# hv_psu_v100_MCU.net
KiCad netlist of a schematic drawn in Altium Designer
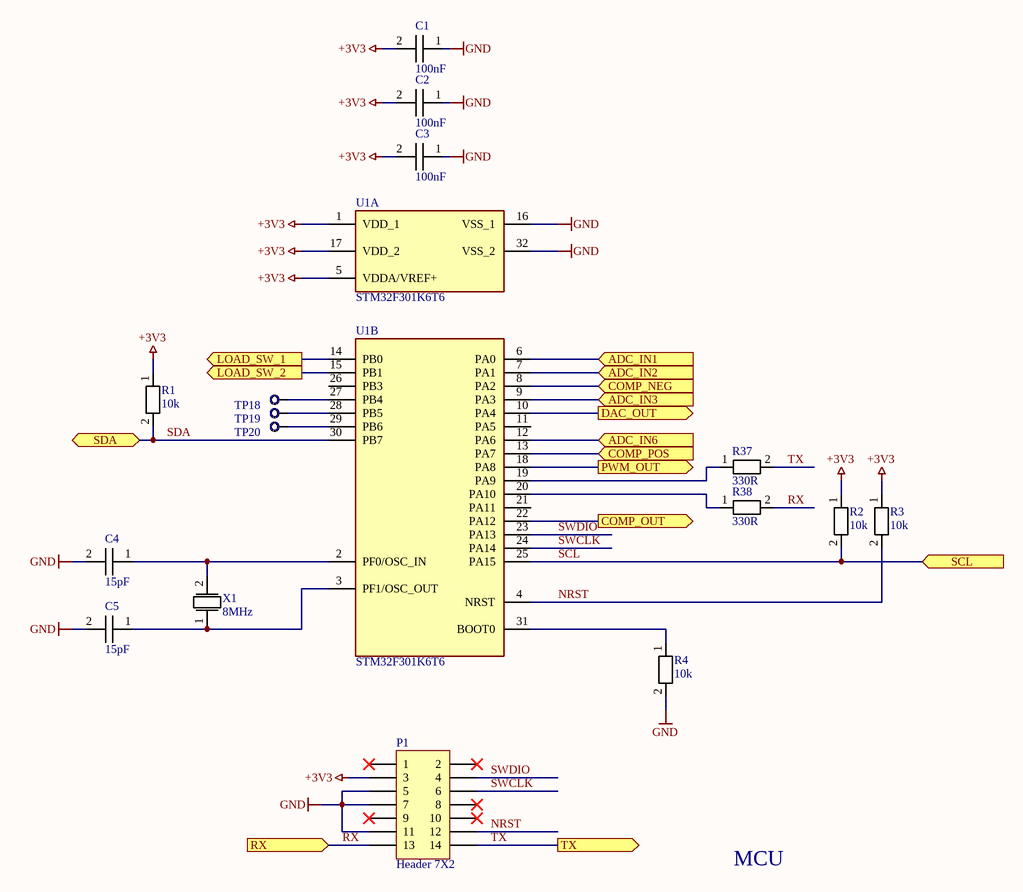
[diagram p0: hv_psu_v100_MCU.SchDoc]

(export (version "E")
  (design (tool "Eeschema 10.0.6"))
  (components
    (comp (ref "C1") (value "100nF") (footprint "1206_C") (libsource (lib "Schlib1") (part "CAPACITOR")))
    (comp (ref "C2") (value "100nF") (footprint "1206_C") (libsource (lib "Schlib1") (part "CAPACITOR")))
    (comp (ref "C3") (value "100nF") (footprint "1206_C") (libsource (lib "Schlib1") (part "CAPACITOR")))
    (comp (ref "C4") (value "15pF") (footprint "1206_C") (libsource (lib "Schlib1") (part "CAPACITOR")))
    (comp (ref "C5") (value "15pF") (footprint "1206_C") (libsource (lib "Schlib1") (part "CAPACITOR")))
    (comp (ref "P1")
      (value "Header 7X2")
      (footprint "HDR2X7")
      (description "Header, 7-Pin, Dual row")
      (fields (field (name "PUBLISHER") "Altium Limited"))
      (libsource (lib "Miscellaneous Connectors") (part "Header 7X2"))
    )
    (comp (ref "R1") (value "10k") (footprint "1206") (libsource (lib "Schlib1") (part "RESISTOR")))
    (comp (ref "R2") (value "10k") (footprint "1206") (libsource (lib "Schlib1") (part "RESISTOR")))
    (comp (ref "R3") (value "10k") (footprint "1206") (libsource (lib "Schlib1") (part "RESISTOR")))
    (comp (ref "R4") (value "10k") (footprint "1206") (libsource (lib "Schlib1") (part "RESISTOR")))
    (comp (ref "R37") (value "330R") (footprint "1206") (libsource (lib "Schlib1") (part "RESISTOR")))
    (comp (ref "R38") (value "330R") (footprint "1206") (libsource (lib "Schlib1") (part "RESISTOR")))
    (comp (ref "TP18") (value "?") (footprint "PAD_40") (libsource (lib "Schlib1") (part "TESTPOINT")))
    (comp (ref "TP19") (value "?") (footprint "PAD_40") (libsource (lib "Schlib1") (part "TESTPOINT")))
    (comp (ref "TP20") (value "?") (footprint "PAD_40") (libsource (lib "Schlib1") (part "TESTPOINT")))
    (comp (ref "U1")
      (value "STM32F301K6T6")
      (footprint "PcbLib1:QFP80P900X900X160-32N")
      (fields (field (name "MOUSER PART NUMBER") "511-STM32F301K6T6"))
      (libsource (lib "ic_modules") (part "STM32F301K6T6"))
    )
    (comp (ref "X1") (value "8MHz") (footprint "XTAL_SMALL") (libsource (lib "Schlib1") (part "XTAL")))
  )
  (nets
    (net (code "1") (name "+3V3") (class "Default")
      (node (ref "C1") (pin "2") (pinfunction "2_2") (pintype "passive"))
      (node (ref "C2") (pin "2") (pinfunction "2_2") (pintype "passive"))
      (node (ref "C3") (pin "2") (pinfunction "2_2") (pintype "passive"))
      (node (ref "P1") (pin "3") (pinfunction "3_3") (pintype "passive"))
      (node (ref "R1") (pin "1") (pinfunction "0_1") (pintype "passive"))
      (node (ref "R2") (pin "1") (pinfunction "0_1") (pintype "passive"))
      (node (ref "R3") (pin "1") (pinfunction "0_1") (pintype "passive"))
      (node (ref "U1") (pin "1") (pinfunction "VDD_1_1") (pintype "passive"))
      (node (ref "U1") (pin "17") (pinfunction "VDD_2_17") (pintype "passive"))
      (node (ref "U1") (pin "5") (pinfunction "VDDA/VREF+_5") (pintype "passive"))
    )
    (net (code "2") (name "/ADC_IN1") (class "Default")
      (node (ref "U1") (pin "6") (pinfunction "PA0_6") (pintype "passive"))
    )
    (net (code "3") (name "/ADC_IN2") (class "Default")
      (node (ref "U1") (pin "7") (pinfunction "PA1_7") (pintype "passive"))
    )
    (net (code "4") (name "/ADC_IN3") (class "Default")
      (node (ref "U1") (pin "9") (pinfunction "PA3_9") (pintype "passive"))
    )
    (net (code "5") (name "/ADC_IN6") (class "Default")
      (node (ref "U1") (pin "12") (pinfunction "PA6_12") (pintype "passive"))
    )
    (net (code "6") (name "/COMP_NEG") (class "Default")
      (node (ref "U1") (pin "8") (pinfunction "PA2_8") (pintype "passive"))
    )
    (net (code "7") (name "/COMP_OUT") (class "Default")
      (node (ref "U1") (pin "22") (pinfunction "PA12_22") (pintype "passive"))
    )
    (net (code "8") (name "/COMP_POS") (class "Default")
      (node (ref "U1") (pin "13") (pinfunction "PA7_13") (pintype "passive"))
    )
    (net (code "9") (name "/DAC_OUT") (class "Default")
      (node (ref "U1") (pin "10") (pinfunction "PA4_10") (pintype "passive"))
    )
    (net (code "10") (name "/LOAD_SW_1") (class "Default")
      (node (ref "U1") (pin "14") (pinfunction "PB0_14") (pintype "passive"))
    )
    (net (code "11") (name "/LOAD_SW_2") (class "Default")
      (node (ref "U1") (pin "15") (pinfunction "PB1_15") (pintype "passive"))
    )
    (net (code "12") (name "/NRST") (class "Default")
      (node (ref "P1") (pin "12") (pinfunction "12_12") (pintype "passive"))
      (node (ref "R3") (pin "2") (pinfunction "1_2") (pintype "passive"))
      (node (ref "U1") (pin "4") (pinfunction "NRST_4") (pintype "passive"))
    )
    (net (code "13") (name "/PWM_OUT") (class "Default")
      (node (ref "U1") (pin "18") (pinfunction "PA8_18") (pintype "passive"))
    )
    (net (code "14") (name "/RX") (class "Default")
      (node (ref "P1") (pin "13") (pinfunction "13_13") (pintype "passive"))
      (node (ref "R38") (pin "2") (pinfunction "1_2") (pintype "passive"))
    )
    (net (code "15") (name "/SCL") (class "Default")
      (node (ref "R2") (pin "2") (pinfunction "1_2") (pintype "passive"))
      (node (ref "U1") (pin "25") (pinfunction "PA15_25") (pintype "passive"))
    )
    (net (code "16") (name "/SDA") (class "Default")
      (node (ref "R1") (pin "2") (pinfunction "1_2") (pintype "passive"))
      (node (ref "U1") (pin "30") (pinfunction "PB7_30") (pintype "passive"))
    )
    (net (code "17") (name "/SWCLK") (class "Default")
      (node (ref "P1") (pin "6") (pinfunction "6_6") (pintype "passive"))
      (node (ref "U1") (pin "24") (pinfunction "PA14_24") (pintype "passive"))
    )
    (net (code "18") (name "/SWDIO") (class "Default")
      (node (ref "P1") (pin "4") (pinfunction "4_4") (pintype "passive"))
      (node (ref "U1") (pin "23") (pinfunction "PA13_23") (pintype "passive"))
    )
    (net (code "19") (name "/TX") (class "Default")
      (node (ref "P1") (pin "14") (pinfunction "14_14") (pintype "passive"))
      (node (ref "R37") (pin "2") (pinfunction "1_2") (pintype "passive"))
    )
    (net (code "20") (name "GND") (class "Default")
      (node (ref "C1") (pin "1") (pinfunction "1_1") (pintype "passive"))
      (node (ref "C2") (pin "1") (pinfunction "1_1") (pintype "passive"))
      (node (ref "C3") (pin "1") (pinfunction "1_1") (pintype "passive"))
      (node (ref "C4") (pin "2") (pinfunction "2_2") (pintype "passive"))
      (node (ref "C5") (pin "2") (pinfunction "2_2") (pintype "passive"))
      (node (ref "P1") (pin "11") (pinfunction "11_11") (pintype "passive"))
      (node (ref "P1") (pin "5") (pinfunction "5_5") (pintype "passive"))
      (node (ref "P1") (pin "7") (pinfunction "7_7") (pintype "passive"))
      (node (ref "R4") (pin "2") (pinfunction "1_2") (pintype "passive"))
      (node (ref "U1") (pin "16") (pinfunction "VSS_1_16") (pintype "passive"))
      (node (ref "U1") (pin "32") (pinfunction "VSS_2_32") (pintype "passive"))
    )
    (net (code "21") (name "Net-(R4-0)") (class "Default")
      (node (ref "R4") (pin "1") (pinfunction "0_1") (pintype "passive"))
      (node (ref "U1") (pin "31") (pinfunction "BOOT0_31") (pintype "passive"))
    )
    (net (code "22") (name "Net-(R37-0)") (class "Default")
      (node (ref "R37") (pin "1") (pinfunction "0_1") (pintype "passive"))
      (node (ref "U1") (pin "19") (pinfunction "PA9_19") (pintype "passive"))
    )
    (net (code "23") (name "Net-(R38-0)") (class "Default")
      (node (ref "R38") (pin "1") (pinfunction "0_1") (pintype "passive"))
      (node (ref "U1") (pin "20") (pinfunction "PA10_20") (pintype "passive"))
    )
    (net (code "24") (name "Net-(U1B-PB4)") (class "Default")
      (node (ref "TP18") (pin "1") (pinfunction "1_1") (pintype "passive"))
      (node (ref "U1") (pin "27") (pinfunction "PB4_27") (pintype "passive"))
    )
    (net (code "25") (name "Net-(U1B-PB5)") (class "Default")
      (node (ref "TP19") (pin "1") (pinfunction "1_1") (pintype "passive"))
      (node (ref "U1") (pin "28") (pinfunction "PB5_28") (pintype "passive"))
    )
    (net (code "26") (name "Net-(U1B-PB6)") (class "Default")
      (node (ref "TP20") (pin "1") (pinfunction "1_1") (pintype "passive"))
      (node (ref "U1") (pin "29") (pinfunction "PB6_29") (pintype "passive"))
    )
    (net (code "27") (name "Net-(U1B-PF0{slash}OSC_IN)") (class "Default")
      (node (ref "C4") (pin "1") (pinfunction "1_1") (pintype "passive"))
      (node (ref "U1") (pin "2") (pinfunction "PF0/OSC_IN_2") (pintype "passive"))
      (node (ref "X1") (pin "2") (pinfunction "2_2") (pintype "passive"))
    )
    (net (code "28") (name "Net-(U1B-PF1{slash}OSC_OUT)") (class "Default")
      (node (ref "C5") (pin "1") (pinfunction "1_1") (pintype "passive"))
      (node (ref "U1") (pin "3") (pinfunction "PF1/OSC_OUT_3") (pintype "passive"))
      (node (ref "X1") (pin "1") (pinfunction "1_1") (pintype "passive"))
    )
    (net (code "29") (name "unconnected-(P1-Pad1)") (class "Default")
      (node (ref "P1") (pin "1") (pinfunction "1_1") (pintype "passive+no_connect"))
    )
    (net (code "30") (name "unconnected-(P1-Pad2)") (class "Default")
      (node (ref "P1") (pin "2") (pinfunction "2_2") (pintype "passive+no_connect"))
    )
    (net (code "31") (name "unconnected-(P1-Pad8)") (class "Default")
      (node (ref "P1") (pin "8") (pinfunction "8_8") (pintype "passive+no_connect"))
    )
    (net (code "32") (name "unconnected-(P1-Pad9)") (class "Default")
      (node (ref "P1") (pin "9") (pinfunction "9_9") (pintype "passive+no_connect"))
    )
    (net (code "33") (name "unconnected-(P1-Pad10)") (class "Default")
      (node (ref "P1") (pin "10") (pinfunction "10_10") (pintype "passive+no_connect"))
    )
    (net (code "34") (name "unconnected-(U1B-PA5-Pad11)") (class "Default")
      (node (ref "U1") (pin "11") (pinfunction "PA5_11") (pintype "passive"))
    )
    (net (code "35") (name "unconnected-(U1B-PA11-Pad21)") (class "Default")
      (node (ref "U1") (pin "21") (pinfunction "PA11_21") (pintype "passive"))
    )
    (net (code "36") (name "unconnected-(U1B-PB3-Pad26)") (class "Default")
      (node (ref "U1") (pin "26") (pinfunction "PB3_26") (pintype "passive"))
    )
  )
)
